# proxi.net
KiCad netlist of a schematic drawn in EAGLE
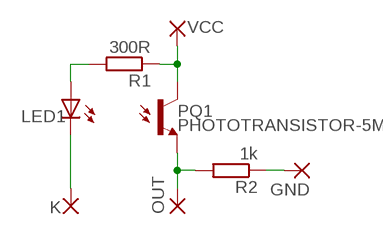
[diagram p0: schematic, sheet 1]

(export (version "E")
  (design (tool "Eeschema 10.0.6"))
  (components
    (comp (ref "GND")
      (value "SMD2")
      (footprint "eagle-import:SMD1,27-2,54")
      (libsource (lib "eagle-import") (part "SMD2"))
    )
    (comp (ref "K")
      (value "SMD2")
      (footprint "eagle-import:SMD1,27-2,54")
      (libsource (lib "eagle-import") (part "SMD2"))
    )
    (comp (ref "LED1")
      (value "LED5MM")
      (footprint "eagle-import:LED5MM")
      (libsource (lib "eagle-import") (part "LED5MM"))
    )
    (comp (ref "OUT")
      (value "SMD2")
      (footprint "eagle-import:SMD1,27-2,54")
      (libsource (lib "eagle-import") (part "SMD2"))
    )
    (comp (ref "PQ1")
      (value "PHOTOTRANSISTOR-5MM")
      (footprint "eagle-import:LED5MM")
      (libsource (lib "eagle-import") (part "PHOTOTRANSISTOR-5MM"))
    )
    (comp (ref "R1")
      (value "300R")
      (footprint "eagle-import:R0805")
      (libsource (lib "eagle-import") (part "R-EU_R0805"))
    )
    (comp (ref "R2")
      (value "1k")
      (footprint "eagle-import:R0805")
      (libsource (lib "eagle-import") (part "R-EU_R0805"))
    )
    (comp (ref "VCC")
      (value "SMD2")
      (footprint "eagle-import:SMD1,27-2,54")
      (libsource (lib "eagle-import") (part "SMD2"))
    )
  )
  (nets
    (net (code "1") (name "Net-(GND-P)") (class "Default")
      (node (ref "GND") (pin "1") (pinfunction "P_1") (pintype "passive"))
      (node (ref "R2") (pin "1") (pinfunction "1_1") (pintype "passive"))
    )
    (net (code "2") (name "Net-(K-P)") (class "Default")
      (node (ref "K") (pin "1") (pinfunction "P_1") (pintype "passive"))
      (node (ref "LED1") (pin "K") (pinfunction "C_K") (pintype "passive"))
    )
    (net (code "3") (name "Net-(LED1-PadA)") (class "Default")
      (node (ref "LED1") (pin "A") (pinfunction "A_A") (pintype "passive"))
      (node (ref "R1") (pin "2") (pinfunction "2_2") (pintype "passive"))
    )
    (net (code "4") (name "Net-(OUT-P)") (class "Default")
      (node (ref "OUT") (pin "1") (pinfunction "P_1") (pintype "passive"))
      (node (ref "PQ1") (pin "A") (pinfunction "E_A") (pintype "passive"))
      (node (ref "R2") (pin "2") (pinfunction "2_2") (pintype "passive"))
    )
    (net (code "5") (name "Net-(PQ1-C)") (class "Default")
      (node (ref "PQ1") (pin "K") (pinfunction "C_K") (pintype "passive"))
      (node (ref "R1") (pin "1") (pinfunction "1_1") (pintype "passive"))
      (node (ref "VCC") (pin "1") (pinfunction "P_1") (pintype "passive"))
    )
  )
)
